# QN9080.net
KiCad netlist of a schematic drawn in Altium Designer
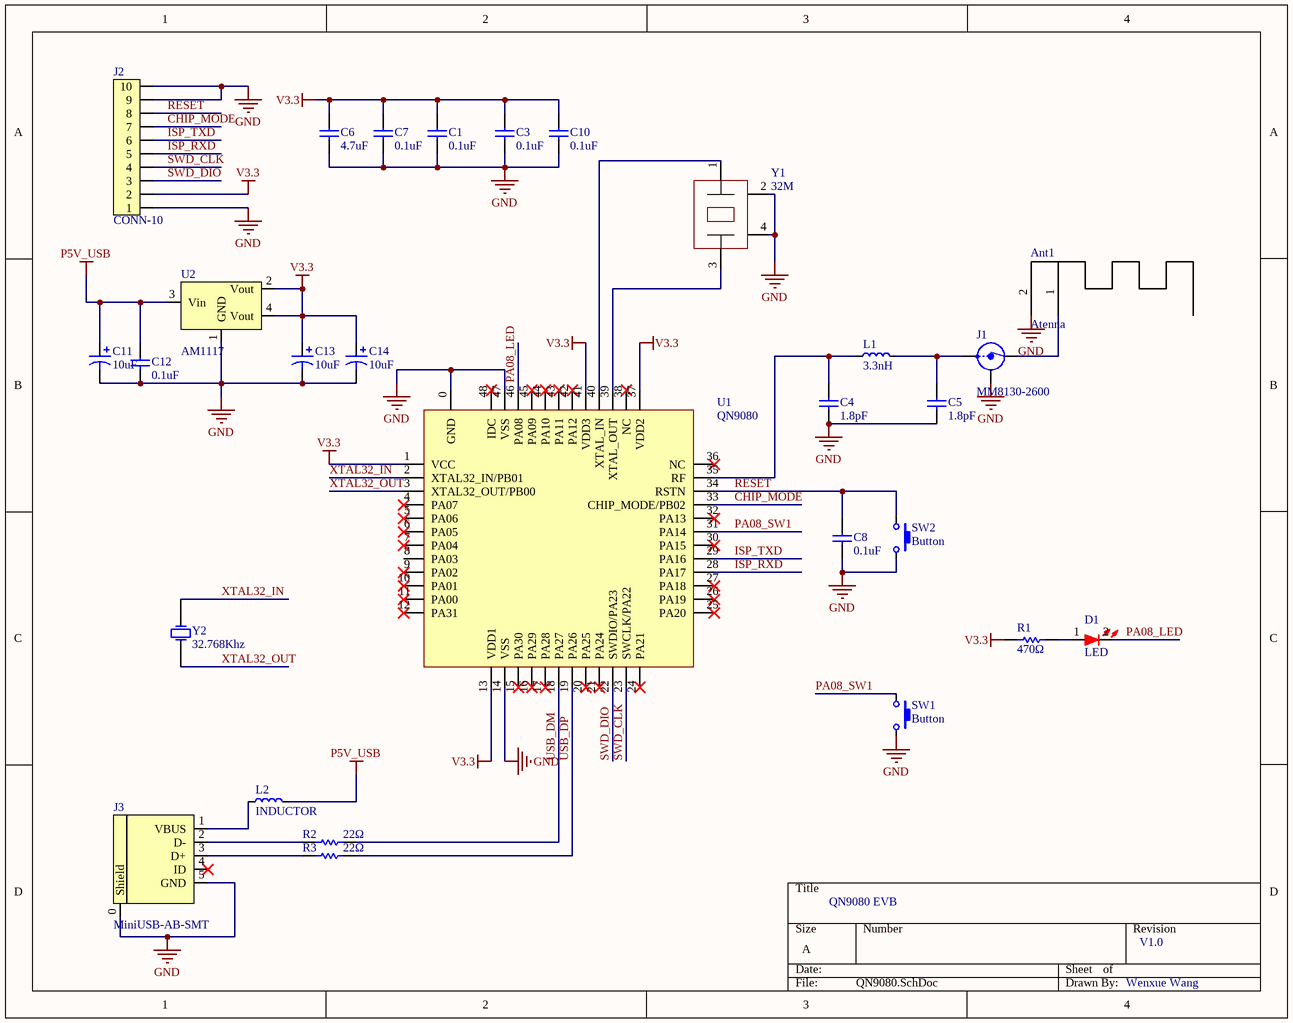
[diagram p0: QN9080.SchDoc]

(export (version "E")
  (design (tool "Eeschema 10.0.6"))
  (components
    (comp (ref "Ant1")
      (value "Atenna")
      (footprint "ANTENNA_IIFA_1")
      (libsource (lib "QN9080") (part "Atenna"))
    )
    (comp (ref "C1")
      (value "0.1uF")
      (footprint "RCL_0603")
      (description "Capacitor")
      (libsource (lib "QN9080") (part "C"))
    )
    (comp (ref "C3")
      (value "0.1uF")
      (footprint "RCL_0603")
      (description "Capacitor")
      (libsource (lib "QN9080") (part "C"))
    )
    (comp (ref "C4")
      (value "1.8pF")
      (footprint "RCL_0603")
      (description "Capacitor")
      (libsource (lib "QN9080") (part "C"))
    )
    (comp (ref "C5")
      (value "1.8pF")
      (footprint "RCL_0603")
      (description "Capacitor")
      (libsource (lib "QN9080") (part "C"))
    )
    (comp (ref "C6")
      (value "4.7uF")
      (footprint "RCL_0603")
      (description "Capacitor")
      (libsource (lib "QN9080") (part "C"))
    )
    (comp (ref "C7")
      (value "0.1uF")
      (footprint "RCL_0603")
      (description "Capacitor")
      (libsource (lib "QN9080") (part "C"))
    )
    (comp (ref "C8")
      (value "0.1uF")
      (footprint "RCL_0603")
      (description "Capacitor")
      (libsource (lib "QN9080") (part "C"))
    )
    (comp (ref "C10")
      (value "0.1uF")
      (footprint "RCL_0603")
      (description "Capacitor")
      (libsource (lib "QN9080") (part "C"))
    )
    (comp (ref "C11") (value "10uF") (footprint "RCL_0805") (libsource (lib "QN9080") (part "CAP_Pol2")))
    (comp (ref "C12")
      (value "0.1uF")
      (footprint "RCL_0603")
      (description "Capacitor")
      (libsource (lib "QN9080") (part "C"))
    )
    (comp (ref "C13") (value "10uF") (footprint "RCL_0805") (libsource (lib "QN9080") (part "CAP_Pol2")))
    (comp (ref "C14") (value "10uF") (footprint "RCL_0805") (libsource (lib "QN9080") (part "CAP_Pol2")))
    (comp (ref "D1") (value "LED") (footprint "LED_0603") (libsource (lib "QN9080") (part "LED")))
    (comp (ref "J1")
      (value "MM8130-2600")
      (footprint "COAXIAL-SWF")
      (description "Coaxial Connector with Switch")
      (libsource (lib "QN9080") (part "Coaxial-Internal-SW"))
    )
    (comp (ref "J2")
      (value "CONN-10")
      (footprint "HDR_1x10")
      (description "Pin List 1x10, 2.54mm (100mil), SMD")
      (libsource (lib "QN9080") (part "CONN-10"))
    )
    (comp (ref "J3")
      (value "MiniUSB-AB-SMT")
      (footprint "USB-Micro-B-RA-SMD-PiP")
      (description "MicroUSB-B-SMT")
      (libsource (lib "QN9080") (part "MiniUSB-AB-SMT"))
    )
    (comp (ref "L1") (value "3.3nH") (footprint "RCL_0402") (libsource (lib "QN9080") (part "INDUCTOR")))
    (comp (ref "L2") (value "INDUCTOR") (footprint "RCL_0603") (libsource (lib "QN9080") (part "INDUCTOR")))
    (comp (ref "R1") (value "470Ω") (footprint "RCL_0603") (libsource (lib "QN9080") (part "Resitor")))
    (comp (ref "R2") (value "22Ω") (footprint "RCL_0603") (libsource (lib "QN9080") (part "Resitor")))
    (comp (ref "R3") (value "22Ω") (footprint "RCL_0603") (libsource (lib "QN9080") (part "Resitor")))
    (comp (ref "SW1") (value "Button") (footprint "E-Switch") (libsource (lib "QN9080") (part "Button")))
    (comp (ref "SW2") (value "Button") (footprint "E-Switch") (libsource (lib "QN9080") (part "Button")))
    (comp (ref "U1") (value "QN9080") (footprint "QN9080QFN48pin") (libsource (lib "QN9080") (part "QN9080")))
    (comp (ref "U2") (value "AM1117") (footprint "SOT-223") (libsource (lib "QN9080") (part "AM1117")))
    (comp (ref "Y1")
      (value "32M")
      (footprint "BT-XTAL_2016")
      (libsource (lib "QN9080") (part "Cystal_32Mhz"))
    )
    (comp (ref "Y2")
      (value "32.768Khz")
      (footprint "XTAL32K_2012")
      (libsource (lib "QN9080") (part "Cystal_32Khz"))
    )
  )
  (nets
    (net (code "1") (name "/CHIP_MODE") (class "Default")
      (node (ref "J2") (pin "7") (pinfunction "7_7") (pintype "passive"))
      (node (ref "U1") (pin "33") (pinfunction "CHIP_MODE/PB02_33") (pintype "passive"))
    )
    (net (code "2") (name "/ISP_RXD") (class "Default")
      (node (ref "J2") (pin "5") (pinfunction "5_5") (pintype "passive"))
      (node (ref "U1") (pin "28") (pinfunction "PA17_28") (pintype "passive"))
    )
    (net (code "3") (name "/ISP_TXD") (class "Default")
      (node (ref "J2") (pin "6") (pinfunction "6_6") (pintype "passive"))
      (node (ref "U1") (pin "29") (pinfunction "PA16_29") (pintype "passive"))
    )
    (net (code "4") (name "/PA08_LED") (class "Default")
      (node (ref "D1") (pin "2") (pinfunction "2_2") (pintype "passive"))
      (node (ref "U1") (pin "46") (pinfunction "PA08_46") (pintype "passive"))
    )
    (net (code "5") (name "/PA08_SW1") (class "Default")
      (node (ref "SW1") (pin "1") (pinfunction "1_1") (pintype "passive"))
      (node (ref "U1") (pin "31") (pinfunction "PA14_31") (pintype "passive"))
    )
    (net (code "6") (name "/RESET") (class "Default")
      (node (ref "C8") (pin "2") (pinfunction "2_2") (pintype "passive"))
      (node (ref "J2") (pin "8") (pinfunction "8_8") (pintype "passive"))
      (node (ref "SW2") (pin "1") (pinfunction "1_1") (pintype "passive"))
      (node (ref "U1") (pin "34") (pinfunction "RSTN_34") (pintype "passive"))
    )
    (net (code "7") (name "/SWD_CLK") (class "Default")
      (node (ref "J2") (pin "4") (pinfunction "4_4") (pintype "passive"))
      (node (ref "U1") (pin "23") (pinfunction "SWCLK/PA22_23") (pintype "passive"))
    )
    (net (code "8") (name "/SWD_DIO") (class "Default")
      (node (ref "J2") (pin "3") (pinfunction "3_3") (pintype "passive"))
      (node (ref "U1") (pin "22") (pinfunction "SWDIO/PA23_22") (pintype "passive"))
    )
    (net (code "9") (name "/USB_DM") (class "Default")
      (node (ref "R2") (pin "1") (pinfunction "1_1") (pintype "passive"))
      (node (ref "U1") (pin "18") (pinfunction "PA27_18") (pintype "passive"))
    )
    (net (code "10") (name "/USB_DP") (class "Default")
      (node (ref "R3") (pin "1") (pinfunction "1_1") (pintype "passive"))
      (node (ref "U1") (pin "19") (pinfunction "PA26_19") (pintype "passive"))
    )
    (net (code "11") (name "/XTAL32_IN") (class "Default")
      (node (ref "U1") (pin "2") (pinfunction "XTAL32_IN/PB01_2") (pintype "passive"))
      (node (ref "Y2") (pin "2") (pinfunction "OSC2_2") (pintype "passive"))
    )
    (net (code "12") (name "/XTAL32_OUT") (class "Default")
      (node (ref "U1") (pin "3") (pinfunction "XTAL32_OUT/PB00_3") (pintype "passive"))
      (node (ref "Y2") (pin "1") (pinfunction "OSC1_1") (pintype "passive"))
    )
    (net (code "13") (name "GND") (class "Default")
      (node (ref "Ant1") (pin "2") (pinfunction "GND_2") (pintype "passive"))
      (node (ref "C1") (pin "1") (pinfunction "1_1") (pintype "passive"))
      (node (ref "C10") (pin "1") (pinfunction "1_1") (pintype "passive"))
      (node (ref "C11") (pin "2") (pinfunction "2_2") (pintype "passive"))
      (node (ref "C12") (pin "1") (pinfunction "1_1") (pintype "passive"))
      (node (ref "C13") (pin "2") (pinfunction "2_2") (pintype "passive"))
      (node (ref "C14") (pin "2") (pinfunction "2_2") (pintype "passive"))
      (node (ref "C3") (pin "1") (pinfunction "1_1") (pintype "passive"))
      (node (ref "C4") (pin "1") (pinfunction "1_1") (pintype "passive"))
      (node (ref "C5") (pin "1") (pinfunction "1_1") (pintype "passive"))
      (node (ref "C6") (pin "1") (pinfunction "1_1") (pintype "passive"))
      (node (ref "C7") (pin "1") (pinfunction "1_1") (pintype "passive"))
      (node (ref "C8") (pin "1") (pinfunction "1_1") (pintype "passive"))
      (node (ref "J1") (pin "2") (pinfunction "Shield_2") (pintype "passive"))
      (node (ref "J2") (pin "1") (pinfunction "1_1") (pintype "passive"))
      (node (ref "J2") (pin "10") (pinfunction "10_10") (pintype "passive"))
      (node (ref "J2") (pin "9") (pinfunction "9_9") (pintype "passive"))
      (node (ref "J3") (pin "0") (pinfunction "Shield_0") (pintype "power_in"))
      (node (ref "J3") (pin "5") (pinfunction "GND_5") (pintype "power_in"))
      (node (ref "SW1") (pin "2") (pinfunction "2_2") (pintype "passive"))
      (node (ref "SW2") (pin "2") (pinfunction "2_2") (pintype "passive"))
      (node (ref "U1") (pin "0") (pinfunction "GND_0") (pintype "passive"))
      (node (ref "U1") (pin "14") (pinfunction "VSS_14") (pintype "passive"))
      (node (ref "U1") (pin "47") (pinfunction "VSS_47") (pintype "passive"))
      (node (ref "U2") (pin "1") (pinfunction "GND_1") (pintype "passive"))
      (node (ref "Y1") (pin "2") (pinfunction "GND_2") (pintype "passive"))
      (node (ref "Y1") (pin "4") (pinfunction "GND_4") (pintype "passive"))
    )
    (net (code "14") (name "Net-(Ant1-ANT)") (class "Default")
      (node (ref "Ant1") (pin "1") (pinfunction "ANT_1") (pintype "passive"))
      (node (ref "J1") (pin "3") (pinfunction "OUT_3") (pintype "passive"))
    )
    (net (code "15") (name "Net-(D1-Pad1)") (class "Default")
      (node (ref "D1") (pin "1") (pinfunction "1_1") (pintype "passive"))
      (node (ref "R1") (pin "1") (pinfunction "1_1") (pintype "passive"))
    )
    (net (code "16") (name "Net-(J1-IN)") (class "Default")
      (node (ref "C5") (pin "2") (pinfunction "2_2") (pintype "passive"))
      (node (ref "J1") (pin "1") (pinfunction "IN_1") (pintype "passive"))
      (node (ref "L1") (pin "2") (pinfunction "2_2") (pintype "passive"))
    )
    (net (code "17") (name "Net-(J3-D+)") (class "Default")
      (node (ref "J3") (pin "3") (pinfunction "D+_3") (pintype "passive"))
      (node (ref "R3") (pin "2") (pinfunction "2_2") (pintype "passive"))
    )
    (net (code "18") (name "Net-(J3-D-)") (class "Default")
      (node (ref "J3") (pin "2") (pinfunction "D-_2") (pintype "passive"))
      (node (ref "R2") (pin "2") (pinfunction "2_2") (pintype "passive"))
    )
    (net (code "19") (name "Net-(J3-VBUS)") (class "Default")
      (node (ref "J3") (pin "1") (pinfunction "VBUS_1") (pintype "power_in"))
      (node (ref "L2") (pin "1") (pinfunction "1_1") (pintype "passive"))
    )
    (net (code "20") (name "Net-(U1-RF)") (class "Default")
      (node (ref "C4") (pin "2") (pinfunction "2_2") (pintype "passive"))
      (node (ref "L1") (pin "1") (pinfunction "1_1") (pintype "passive"))
      (node (ref "U1") (pin "35") (pinfunction "RF_35") (pintype "passive"))
    )
    (net (code "21") (name "Net-(U1-XTAL_IN)") (class "Default")
      (node (ref "U1") (pin "40") (pinfunction "XTAL_IN_40") (pintype "passive"))
      (node (ref "Y1") (pin "1") (pinfunction "XTAL1_1") (pintype "passive"))
    )
    (net (code "22") (name "Net-(U1-XTAL_OUT)") (class "Default")
      (node (ref "U1") (pin "39") (pinfunction "XTAL_OUT_39") (pintype "passive"))
      (node (ref "Y1") (pin "3") (pinfunction "XTAL2_3") (pintype "passive"))
    )
    (net (code "23") (name "P5V_USB") (class "Default")
      (node (ref "C11") (pin "1") (pinfunction "1_1") (pintype "passive"))
      (node (ref "C12") (pin "2") (pinfunction "2_2") (pintype "passive"))
      (node (ref "L2") (pin "2") (pinfunction "2_2") (pintype "passive"))
      (node (ref "U2") (pin "3") (pinfunction "Vin_3") (pintype "passive"))
    )
    (net (code "24") (name "V3.3") (class "Default")
      (node (ref "C1") (pin "2") (pinfunction "2_2") (pintype "passive"))
      (node (ref "C10") (pin "2") (pinfunction "2_2") (pintype "passive"))
      (node (ref "C13") (pin "1") (pinfunction "1_1") (pintype "passive"))
      (node (ref "C14") (pin "1") (pinfunction "1_1") (pintype "passive"))
      (node (ref "C3") (pin "2") (pinfunction "2_2") (pintype "passive"))
      (node (ref "C6") (pin "2") (pinfunction "2_2") (pintype "passive"))
      (node (ref "C7") (pin "2") (pinfunction "2_2") (pintype "passive"))
      (node (ref "J2") (pin "2") (pinfunction "2_2") (pintype "passive"))
      (node (ref "R1") (pin "2") (pinfunction "2_2") (pintype "passive"))
      (node (ref "U1") (pin "1") (pinfunction "VCC_1") (pintype "passive"))
      (node (ref "U1") (pin "13") (pinfunction "VDD1_13") (pintype "passive"))
      (node (ref "U1") (pin "37") (pinfunction "VDD2_37") (pintype "passive"))
      (node (ref "U1") (pin "41") (pinfunction "VDD3_41") (pintype "passive"))
      (node (ref "U2") (pin "2") (pinfunction "Vout_2") (pintype "passive"))
      (node (ref "U2") (pin "4") (pinfunction "Vout_4") (pintype "passive"))
    )
    (net (code "25") (name "unconnected-(J3-ID-Pad4)") (class "Default")
      (node (ref "J3") (pin "4") (pinfunction "ID_4") (pintype "passive+no_connect"))
    )
    (net (code "26") (name "unconnected-(U1-IDC-Pad48)") (class "Default")
      (node (ref "U1") (pin "48") (pinfunction "IDC_48") (pintype "passive+no_connect"))
    )
    (net (code "27") (name "unconnected-(U1-NC-Pad36)") (class "Default")
      (node (ref "U1") (pin "36") (pinfunction "NC_36") (pintype "passive+no_connect"))
    )
    (net (code "28") (name "unconnected-(U1-NC-Pad38)") (class "Default")
      (node (ref "U1") (pin "38") (pinfunction "NC_38") (pintype "passive+no_connect"))
    )
    (net (code "29") (name "unconnected-(U1-PA00-Pad11)") (class "Default")
      (node (ref "U1") (pin "11") (pinfunction "PA00_11") (pintype "passive+no_connect"))
    )
    (net (code "30") (name "unconnected-(U1-PA01-Pad10)") (class "Default")
      (node (ref "U1") (pin "10") (pinfunction "PA01_10") (pintype "passive+no_connect"))
    )
    (net (code "31") (name "unconnected-(U1-PA02-Pad9)") (class "Default")
      (node (ref "U1") (pin "9") (pinfunction "PA02_9") (pintype "passive+no_connect"))
    )
    (net (code "32") (name "unconnected-(U1-PA03-Pad8)") (class "Default")
      (node (ref "U1") (pin "8") (pinfunction "PA03_8") (pintype "passive"))
    )
    (net (code "33") (name "unconnected-(U1-PA04-Pad7)") (class "Default")
      (node (ref "U1") (pin "7") (pinfunction "PA04_7") (pintype "passive+no_connect"))
    )
    (net (code "34") (name "unconnected-(U1-PA05-Pad6)") (class "Default")
      (node (ref "U1") (pin "6") (pinfunction "PA05_6") (pintype "passive+no_connect"))
    )
    (net (code "35") (name "unconnected-(U1-PA06-Pad5)") (class "Default")
      (node (ref "U1") (pin "5") (pinfunction "PA06_5") (pintype "passive+no_connect"))
    )
    (net (code "36") (name "unconnected-(U1-PA07-Pad4)") (class "Default")
      (node (ref "U1") (pin "4") (pinfunction "PA07_4") (pintype "passive+no_connect"))
    )
    (net (code "37") (name "unconnected-(U1-PA09-Pad45)") (class "Default")
      (node (ref "U1") (pin "45") (pinfunction "PA09_45") (pintype "passive+no_connect"))
    )
    (net (code "38") (name "unconnected-(U1-PA10-Pad44)") (class "Default")
      (node (ref "U1") (pin "44") (pinfunction "PA10_44") (pintype "passive+no_connect"))
    )
    (net (code "39") (name "unconnected-(U1-PA11-Pad43)") (class "Default")
      (node (ref "U1") (pin "43") (pinfunction "PA11_43") (pintype "passive+no_connect"))
    )
    (net (code "40") (name "unconnected-(U1-PA12-Pad42)") (class "Default")
      (node (ref "U1") (pin "42") (pinfunction "PA12_42") (pintype "passive+no_connect"))
    )
    (net (code "41") (name "unconnected-(U1-PA13-Pad32)") (class "Default")
      (node (ref "U1") (pin "32") (pinfunction "PA13_32") (pintype "passive+no_connect"))
    )
    (net (code "42") (name "unconnected-(U1-PA15-Pad30)") (class "Default")
      (node (ref "U1") (pin "30") (pinfunction "PA15_30") (pintype "passive+no_connect"))
    )
    (net (code "43") (name "unconnected-(U1-PA18-Pad27)") (class "Default")
      (node (ref "U1") (pin "27") (pinfunction "PA18_27") (pintype "passive+no_connect"))
    )
    (net (code "44") (name "unconnected-(U1-PA19-Pad26)") (class "Default")
      (node (ref "U1") (pin "26") (pinfunction "PA19_26") (pintype "passive+no_connect"))
    )
    (net (code "45") (name "unconnected-(U1-PA20-Pad25)") (class "Default")
      (node (ref "U1") (pin "25") (pinfunction "PA20_25") (pintype "passive+no_connect"))
    )
    (net (code "46") (name "unconnected-(U1-PA21-Pad24)") (class "Default")
      (node (ref "U1") (pin "24") (pinfunction "PA21_24") (pintype "passive+no_connect"))
    )
    (net (code "47") (name "unconnected-(U1-PA24-Pad21)") (class "Default")
      (node (ref "U1") (pin "21") (pinfunction "PA24_21") (pintype "passive+no_connect"))
    )
    (net (code "48") (name "unconnected-(U1-PA25-Pad20)") (class "Default")
      (node (ref "U1") (pin "20") (pinfunction "PA25_20") (pintype "passive+no_connect"))
    )
    (net (code "49") (name "unconnected-(U1-PA28-Pad17)") (class "Default")
      (node (ref "U1") (pin "17") (pinfunction "PA28_17") (pintype "passive+no_connect"))
    )
    (net (code "50") (name "unconnected-(U1-PA29-Pad16)") (class "Default")
      (node (ref "U1") (pin "16") (pinfunction "PA29_16") (pintype "passive+no_connect"))
    )
    (net (code "51") (name "unconnected-(U1-PA30-Pad15)") (class "Default")
      (node (ref "U1") (pin "15") (pinfunction "PA30_15") (pintype "passive+no_connect"))
    )
    (net (code "52") (name "unconnected-(U1-PA31-Pad12)") (class "Default")
      (node (ref "U1") (pin "12") (pinfunction "PA31_12") (pintype "passive+no_connect"))
    )
  )
)
